# WeatherBoard.net
KiCad netlist of a schematic drawn in EAGLE
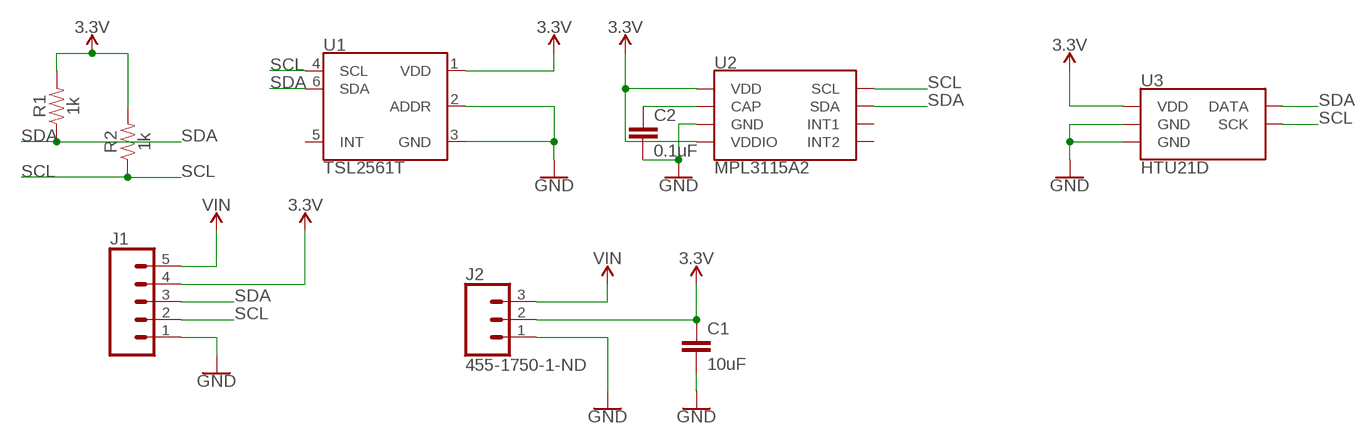
[diagram p0: schematic, sheet 1]

(export (version "E")
  (design (tool "Eeschema 10.0.6"))
  (components
    (comp (ref "C1")
      (value "10uF")
      (footprint "eagle-import:1206")
      (libsource (lib "eagle-import") (part "10UF-1206-6.3V-20%"))
    )
    (comp (ref "C2")
      (value "0.1uF")
      (footprint "eagle-import:0603")
      (libsource (lib "eagle-import") (part "0.1UF-0603-25V-5%"))
    )
    (comp (ref "J1")
      (value "CONN_05")
      (footprint "eagle-import:1X05")
      (libsource (lib "eagle-import") (part "CONN_05"))
    )
    (comp (ref "J2")
      (value "455-1750-1-ND")
      (footprint "eagle-import:1X03")
      (libsource (lib "eagle-import") (part "CONN_03"))
    )
    (comp (ref "R1")
      (value "1k")
      (footprint "eagle-import:0603")
      (libsource (lib "eagle-import") (part "1KOHM-0603-1/10W-1%"))
    )
    (comp (ref "R2")
      (value "1k")
      (footprint "eagle-import:0603")
      (libsource (lib "eagle-import") (part "1KOHM-0603-1/10W-1%"))
    )
    (comp (ref "U1")
      (value "TSL2561T")
      (footprint "eagle-import:TMB-6")
      (libsource (lib "eagle-import") (part "TSL2561T"))
    )
    (comp (ref "U2")
      (value "MPL3115A2")
      (footprint "eagle-import:LGA-8-5X3")
      (libsource (lib "eagle-import") (part "MPL3115A2"))
    )
    (comp (ref "U3")
      (value "HTU21D")
      (footprint "eagle-import:DFN-6-3X3-HTU21D")
      (libsource (lib "eagle-import") (part "HTU21D"))
    )
  )
  (nets
    (net (code "1") (name "/SCL") (class "Default")
      (node (ref "J1") (pin "2") (pinfunction "2_2") (pintype "passive"))
      (node (ref "R2") (pin "1") (pinfunction "1_1") (pintype "passive"))
      (node (ref "U1") (pin "4") (pinfunction "SCL_4") (pintype "input"))
      (node (ref "U2") (pin "8") (pinfunction "SCL_8") (pintype "bidirectional"))
      (node (ref "U3") (pin "SCK") (pinfunction "SCK_SCK") (pintype "input"))
    )
    (net (code "2") (name "/SDA") (class "Default")
      (node (ref "J1") (pin "3") (pinfunction "3_3") (pintype "passive"))
      (node (ref "R1") (pin "1") (pinfunction "1_1") (pintype "passive"))
      (node (ref "U1") (pin "6") (pinfunction "SDA_6") (pintype "bidirectional"))
      (node (ref "U2") (pin "7") (pinfunction "SDA_7") (pintype "bidirectional"))
      (node (ref "U3") (pin "DATA") (pinfunction "DATA_DATA") (pintype "bidirectional"))
    )
    (net (code "3") (name "3.3V") (class "Default")
      (node (ref "C1") (pin "1") (pinfunction "1_1") (pintype "passive"))
      (node (ref "J1") (pin "4") (pinfunction "4_4") (pintype "passive"))
      (node (ref "J2") (pin "2") (pinfunction "2_2") (pintype "passive"))
      (node (ref "R1") (pin "2") (pinfunction "2_2") (pintype "passive"))
      (node (ref "R2") (pin "2") (pinfunction "2_2") (pintype "passive"))
      (node (ref "U1") (pin "1") (pinfunction "VDD_1") (pintype "power_in"))
      (node (ref "U2") (pin "1") (pinfunction "VDD_1") (pintype "power_in"))
      (node (ref "U2") (pin "4") (pinfunction "VDDIO_4") (pintype "power_in"))
      (node (ref "U3") (pin "VDD") (pinfunction "VDD_VDD") (pintype "power_in"))
    )
    (net (code "4") (name "GND") (class "Default")
      (node (ref "C1") (pin "2") (pinfunction "2_2") (pintype "passive"))
      (node (ref "C2") (pin "2") (pinfunction "2_2") (pintype "passive"))
      (node (ref "J1") (pin "1") (pinfunction "1_1") (pintype "passive"))
      (node (ref "J2") (pin "1") (pinfunction "1_1") (pintype "passive"))
      (node (ref "U1") (pin "2") (pinfunction "ADDR_2") (pintype "input"))
      (node (ref "U1") (pin "3") (pinfunction "GND_3") (pintype "power_in"))
      (node (ref "U2") (pin "3") (pinfunction "GND_3") (pintype "power_in"))
      (node (ref "U3") (pin "7") (pinfunction "GND_7") (pintype "power_in"))
      (node (ref "U3") (pin "GND") (pinfunction "GND_GND") (pintype "power_in"))
    )
    (net (code "5") (name "Net-(U2-CAP)") (class "Default")
      (node (ref "C2") (pin "1") (pinfunction "1_1") (pintype "passive"))
      (node (ref "U2") (pin "2") (pinfunction "CAP_2") (pintype "power_in"))
    )
    (net (code "6") (name "VIN") (class "Default")
      (node (ref "J1") (pin "5") (pinfunction "5_5") (pintype "passive"))
      (node (ref "J2") (pin "3") (pinfunction "3_3") (pintype "passive"))
    )
    (net (code "7") (name "unconnected-(U1-INT-Pad5)") (class "Default")
      (node (ref "U1") (pin "5") (pinfunction "INT_5") (pintype "output"))
    )
    (net (code "8") (name "unconnected-(U2-INT1-Pad6)") (class "Default")
      (node (ref "U2") (pin "6") (pinfunction "INT1_6") (pintype "output"))
    )
    (net (code "9") (name "unconnected-(U2-INT2-Pad5)") (class "Default")
      (node (ref "U2") (pin "5") (pinfunction "INT2_5") (pintype "output"))
    )
  )
)
